# ProPrj___2024-10-24-09-22-03.net
KiCad netlist of a schematic drawn in EasyEDA Pro
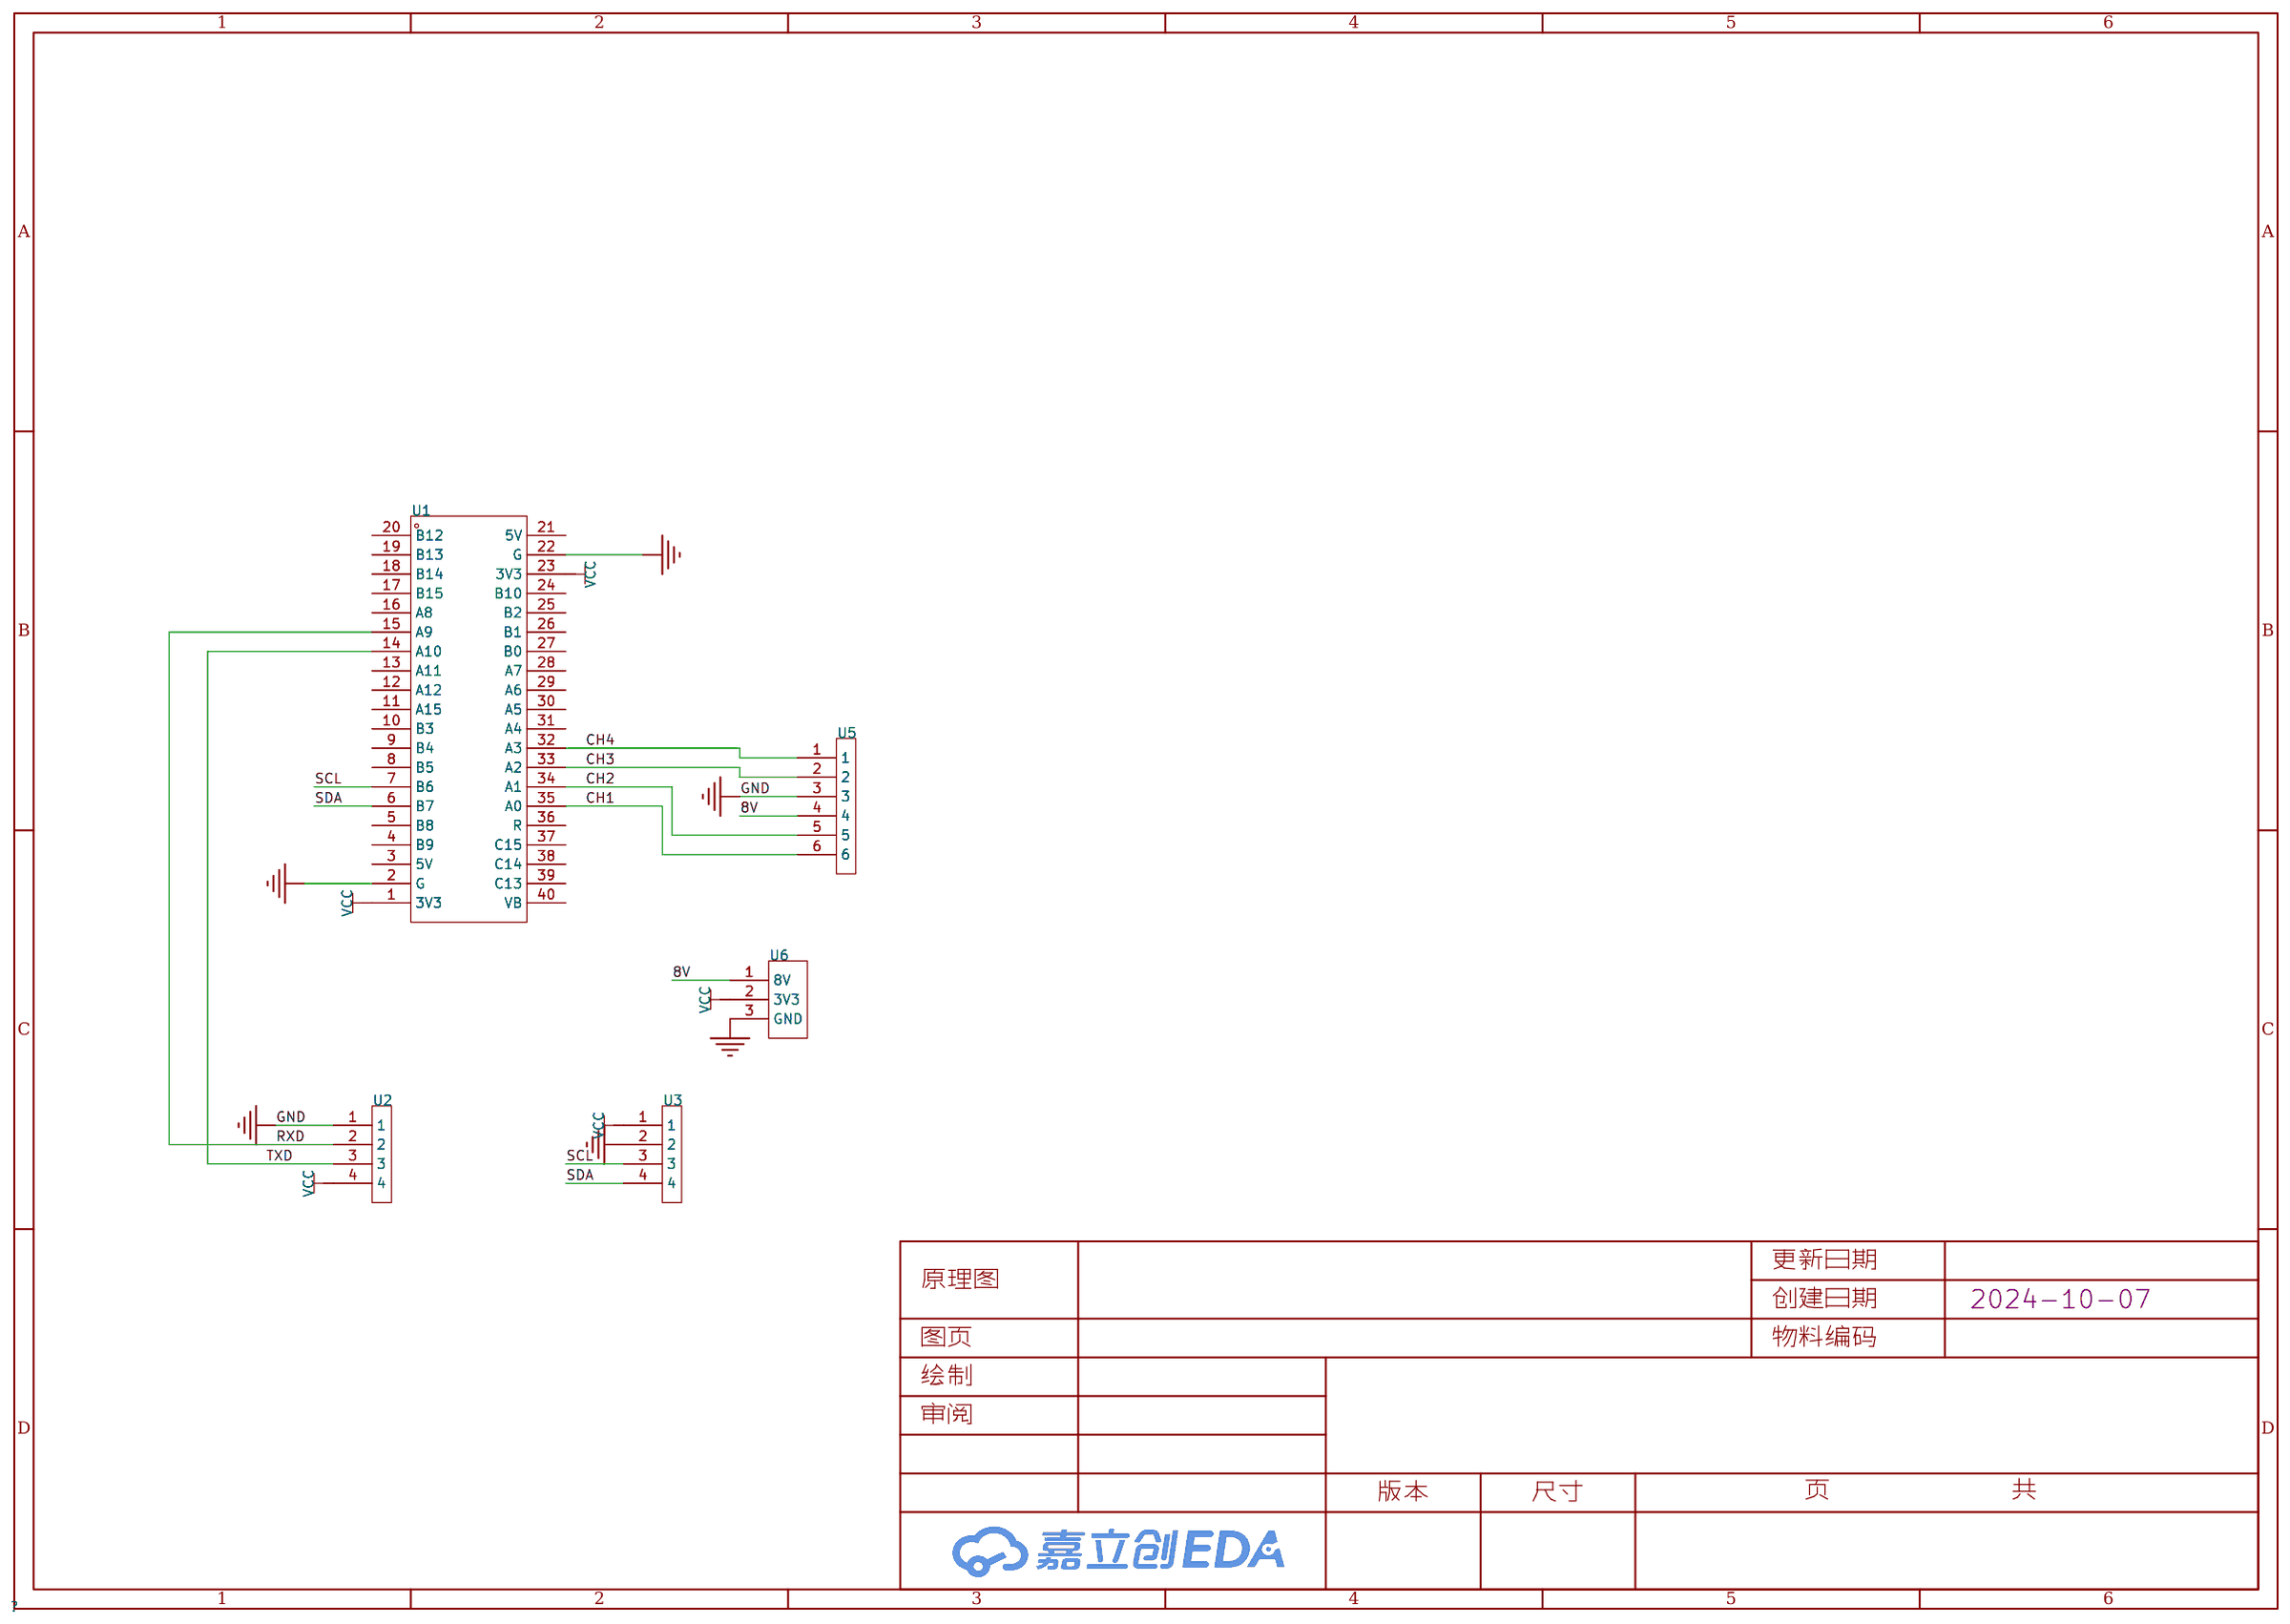
[diagram p0: schematic sheet]

(export (version "E")
  (design (tool "Eeschema 10.0.6"))
  (components
    (comp (ref "U1") (value "~") (footprint "easyedapro:不知道") (libsource (lib "easyedapro") (part "ccu6")))
    (comp (ref "U2") (value "~") (footprint "easyedapro:4pin") (libsource (lib "easyedapro") (part "4pin")))
    (comp (ref "U3") (value "~") (footprint "easyedapro:4pin") (libsource (lib "easyedapro") (part "4pin")))
    (comp (ref "U5") (value "~") (footprint "easyedapro:6pin") (libsource (lib "easyedapro") (part "6pin")))
    (comp (ref "U6") (value "~") (footprint "easyedapro:供电PIN") (libsource (lib "easyedapro") (part "供电PIN")))
  )
  (nets
    (net (code "1") (name "/8V") (class "Default")
      (node (ref "U5") (pin "4") (pinfunction "4_4") (pintype "input"))
      (node (ref "U6") (pin "1") (pinfunction "8V_1") (pintype "input"))
    )
    (net (code "2") (name "/CH1") (class "Default")
      (node (ref "U1") (pin "35") (pinfunction "A0_35") (pintype "input"))
      (node (ref "U5") (pin "6") (pinfunction "6_6") (pintype "input"))
    )
    (net (code "3") (name "/CH2") (class "Default")
      (node (ref "U1") (pin "34") (pinfunction "A1_34") (pintype "input"))
      (node (ref "U5") (pin "5") (pinfunction "5_5") (pintype "input"))
    )
    (net (code "4") (name "/CH3") (class "Default")
      (node (ref "U1") (pin "33") (pinfunction "A2_33") (pintype "input"))
      (node (ref "U5") (pin "2") (pinfunction "2_2") (pintype "input"))
    )
    (net (code "5") (name "/CH4") (class "Default")
      (node (ref "U1") (pin "32") (pinfunction "A3_32") (pintype "input"))
      (node (ref "U5") (pin "1") (pinfunction "1_1") (pintype "input"))
    )
    (net (code "6") (name "/RXD") (class "Default")
      (node (ref "U1") (pin "15") (pinfunction "A9_15") (pintype "input"))
      (node (ref "U2") (pin "2") (pinfunction "2_2") (pintype "input"))
    )
    (net (code "7") (name "/SCL") (class "Default")
      (node (ref "U1") (pin "7") (pinfunction "B6_7") (pintype "input"))
      (node (ref "U3") (pin "3") (pinfunction "3_3") (pintype "input"))
    )
    (net (code "8") (name "/SDA") (class "Default")
      (node (ref "U1") (pin "6") (pinfunction "B7_6") (pintype "input"))
      (node (ref "U3") (pin "4") (pinfunction "4_4") (pintype "input"))
    )
    (net (code "9") (name "/TXD") (class "Default")
      (node (ref "U1") (pin "14") (pinfunction "A10_14") (pintype "input"))
      (node (ref "U2") (pin "3") (pinfunction "3_3") (pintype "input"))
    )
    (net (code "10") (name "GND") (class "Default")
      (node (ref "U1") (pin "2") (pinfunction "G_2") (pintype "input"))
      (node (ref "U1") (pin "22") (pinfunction "G_22") (pintype "input"))
      (node (ref "U2") (pin "1") (pinfunction "1_1") (pintype "input"))
      (node (ref "U3") (pin "2") (pinfunction "2_2") (pintype "input"))
      (node (ref "U5") (pin "3") (pinfunction "3_3") (pintype "input"))
      (node (ref "U6") (pin "3") (pinfunction "GND_3") (pintype "input"))
    )
    (net (code "11") (name "VCC") (class "Default")
      (node (ref "U1") (pin "1") (pinfunction "3V3_1") (pintype "input"))
      (node (ref "U1") (pin "23") (pinfunction "3V3_23") (pintype "input"))
      (node (ref "U2") (pin "4") (pinfunction "4_4") (pintype "input"))
      (node (ref "U3") (pin "1") (pinfunction "1_1") (pintype "input"))
      (node (ref "U6") (pin "2") (pinfunction "3V3_2") (pintype "input"))
    )
    (net (code "12") (name "unconnected-(U1-5V-Pad3)") (class "Default")
      (node (ref "U1") (pin "3") (pinfunction "5V_3") (pintype "input"))
    )
    (net (code "13") (name "unconnected-(U1-5V-Pad21)") (class "Default")
      (node (ref "U1") (pin "21") (pinfunction "5V_21") (pintype "input"))
    )
    (net (code "14") (name "unconnected-(U1-A4-Pad31)") (class "Default")
      (node (ref "U1") (pin "31") (pinfunction "A4_31") (pintype "input"))
    )
    (net (code "15") (name "unconnected-(U1-A5-Pad30)") (class "Default")
      (node (ref "U1") (pin "30") (pinfunction "A5_30") (pintype "input"))
    )
    (net (code "16") (name "unconnected-(U1-A6-Pad29)") (class "Default")
      (node (ref "U1") (pin "29") (pinfunction "A6_29") (pintype "input"))
    )
    (net (code "17") (name "unconnected-(U1-A7-Pad28)") (class "Default")
      (node (ref "U1") (pin "28") (pinfunction "A7_28") (pintype "input"))
    )
    (net (code "18") (name "unconnected-(U1-A8-Pad16)") (class "Default")
      (node (ref "U1") (pin "16") (pinfunction "A8_16") (pintype "input"))
    )
    (net (code "19") (name "unconnected-(U1-A11-Pad13)") (class "Default")
      (node (ref "U1") (pin "13") (pinfunction "A11_13") (pintype "input"))
    )
    (net (code "20") (name "unconnected-(U1-A12-Pad12)") (class "Default")
      (node (ref "U1") (pin "12") (pinfunction "A12_12") (pintype "input"))
    )
    (net (code "21") (name "unconnected-(U1-A15-Pad11)") (class "Default")
      (node (ref "U1") (pin "11") (pinfunction "A15_11") (pintype "input"))
    )
    (net (code "22") (name "unconnected-(U1-B0-Pad27)") (class "Default")
      (node (ref "U1") (pin "27") (pinfunction "B0_27") (pintype "input"))
    )
    (net (code "23") (name "unconnected-(U1-B1-Pad26)") (class "Default")
      (node (ref "U1") (pin "26") (pinfunction "B1_26") (pintype "input"))
    )
    (net (code "24") (name "unconnected-(U1-B2-Pad25)") (class "Default")
      (node (ref "U1") (pin "25") (pinfunction "B2_25") (pintype "input"))
    )
    (net (code "25") (name "unconnected-(U1-B3-Pad10)") (class "Default")
      (node (ref "U1") (pin "10") (pinfunction "B3_10") (pintype "input"))
    )
    (net (code "26") (name "unconnected-(U1-B4-Pad9)") (class "Default")
      (node (ref "U1") (pin "9") (pinfunction "B4_9") (pintype "input"))
    )
    (net (code "27") (name "unconnected-(U1-B5-Pad8)") (class "Default")
      (node (ref "U1") (pin "8") (pinfunction "B5_8") (pintype "input"))
    )
    (net (code "28") (name "unconnected-(U1-B8-Pad5)") (class "Default")
      (node (ref "U1") (pin "5") (pinfunction "B8_5") (pintype "input"))
    )
    (net (code "29") (name "unconnected-(U1-B9-Pad4)") (class "Default")
      (node (ref "U1") (pin "4") (pinfunction "B9_4") (pintype "input"))
    )
    (net (code "30") (name "unconnected-(U1-B10-Pad24)") (class "Default")
      (node (ref "U1") (pin "24") (pinfunction "B10_24") (pintype "input"))
    )
    (net (code "31") (name "unconnected-(U1-B12-Pad20)") (class "Default")
      (node (ref "U1") (pin "20") (pinfunction "B12_20") (pintype "input"))
    )
    (net (code "32") (name "unconnected-(U1-B13-Pad19)") (class "Default")
      (node (ref "U1") (pin "19") (pinfunction "B13_19") (pintype "input"))
    )
    (net (code "33") (name "unconnected-(U1-B14-Pad18)") (class "Default")
      (node (ref "U1") (pin "18") (pinfunction "B14_18") (pintype "input"))
    )
    (net (code "34") (name "unconnected-(U1-B15-Pad17)") (class "Default")
      (node (ref "U1") (pin "17") (pinfunction "B15_17") (pintype "input"))
    )
    (net (code "35") (name "unconnected-(U1-C13-Pad39)") (class "Default")
      (node (ref "U1") (pin "39") (pinfunction "C13_39") (pintype "input"))
    )
    (net (code "36") (name "unconnected-(U1-C14-Pad38)") (class "Default")
      (node (ref "U1") (pin "38") (pinfunction "C14_38") (pintype "input"))
    )
    (net (code "37") (name "unconnected-(U1-C15-Pad37)") (class "Default")
      (node (ref "U1") (pin "37") (pinfunction "C15_37") (pintype "input"))
    )
    (net (code "38") (name "unconnected-(U1-R-Pad36)") (class "Default")
      (node (ref "U1") (pin "36") (pinfunction "R_36") (pintype "input"))
    )
    (net (code "39") (name "unconnected-(U1-VB-Pad40)") (class "Default")
      (node (ref "U1") (pin "40") (pinfunction "VB_40") (pintype "input"))
    )
  )
)
